# tornado-shield.net
KiCad netlist of a schematic drawn in EAGLE
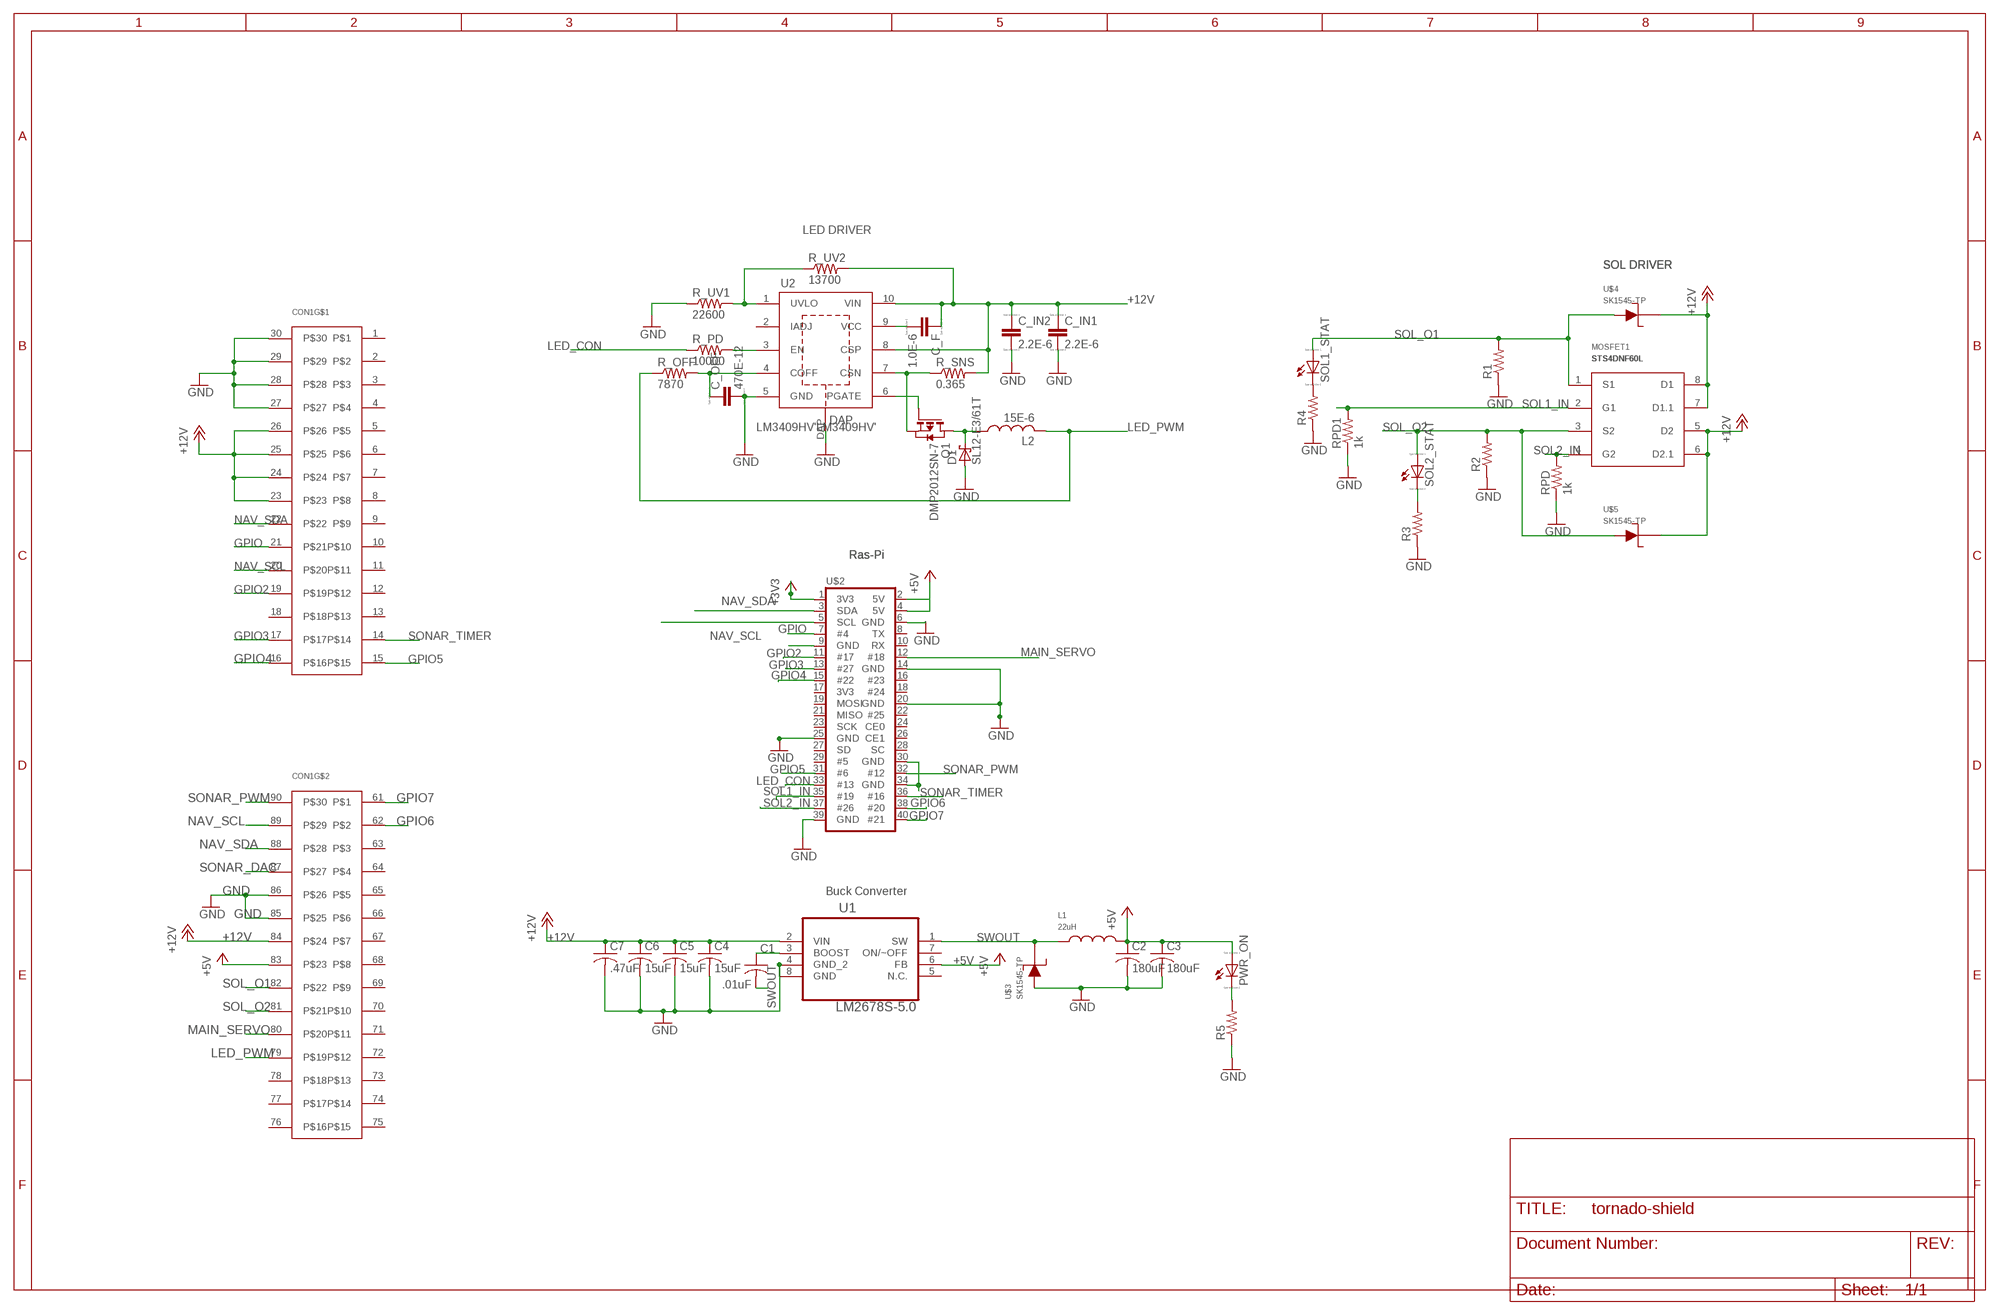
[diagram p0: schematic, sheet 1]

(export (version "E")
  (design (tool "Eeschema 10.0.6"))
  (components
    (comp (ref "C1")
      (value ".01uF")
      (footprint "eagle-import:C0603")
      (libsource (lib "eagle-import") (part "C-USC0603"))
    )
    (comp (ref "C2")
      (value "180uF")
      (footprint "eagle-import:C0603")
      (libsource (lib "eagle-import") (part "C-USC0603"))
    )
    (comp (ref "C3")
      (value "180uF")
      (footprint "eagle-import:C0603")
      (libsource (lib "eagle-import") (part "C-USC0603"))
    )
    (comp (ref "C4")
      (value "15uF")
      (footprint "eagle-import:C0603")
      (libsource (lib "eagle-import") (part "C-USC0603"))
    )
    (comp (ref "C5")
      (value "15uF")
      (footprint "eagle-import:C0603")
      (libsource (lib "eagle-import") (part "C-USC0603"))
    )
    (comp (ref "C6")
      (value "15uF")
      (footprint "eagle-import:C0603")
      (libsource (lib "eagle-import") (part "C-USC0603"))
    )
    (comp (ref "C7")
      (value ".47uF")
      (footprint "eagle-import:C0603")
      (libsource (lib "eagle-import") (part "C-USC0603"))
    )
    (comp (ref "CON1")
      (value "ROV_SHIELD_V2")
      (footprint "eagle-import:ROV_SHIELD_V2")
      (libsource (lib "eagle-import") (part "ROV_SHIELD_V2"))
    )
    (comp (ref "C_F")
      (value "1.0E-6")
      (footprint "eagle-import:C0603")
      (libsource (lib "eagle-import") (part "CC0603"))
    )
    (comp (ref "C_IN1")
      (value "2.2E-6")
      (footprint "eagle-import:C0603")
      (libsource (lib "eagle-import") (part "CC0603"))
    )
    (comp (ref "C_IN2")
      (value "2.2E-6")
      (footprint "eagle-import:C0603")
      (libsource (lib "eagle-import") (part "CC0603"))
    )
    (comp (ref "C_OFF")
      (value "470E-12")
      (footprint "eagle-import:C0402")
      (libsource (lib "eagle-import") (part "CC0402"))
    )
    (comp (ref "D1")
      (value "SL12-E3/61T")
      (footprint "eagle-import:SL12-E3_61T")
      (libsource (lib "eagle-import") (part "SL12-E3/61T"))
    )
    (comp (ref "L1")
      (value "22uH")
      (footprint "eagle-import:7443551221")
      (libsource (lib "eagle-import") (part "L_7443551221"))
    )
    (comp (ref "L2")
      (value "15E-6")
      (footprint "eagle-import:SRN8040")
      (libsource (lib "eagle-import") (part "SRN8040"))
    )
    (comp (ref "MOSFET1")
      (value "STS4DNF60L")
      (footprint "eagle-import:SO08")
      (libsource (lib "eagle-import") (part "STS4DNF60L"))
    )
    (comp (ref "PWR_ON")
      (value "LED_ESML0603")
      (footprint "eagle-import:LED_SML0603")
      (libsource (lib "eagle-import") (part "LED_ESML0603"))
    )
    (comp (ref "Q1")
      (value "DMP2012SN-7")
      (footprint "eagle-import:DMP2012SN-7")
      (libsource (lib "eagle-import") (part "DMP2012SN-7"))
    )
    (comp (ref "R1")
      (value "R-US_R0603")
      (footprint "eagle-import:R0603")
      (libsource (lib "eagle-import") (part "rcl_R-US_R0603"))
    )
    (comp (ref "R2")
      (value "R-US_R0603")
      (footprint "eagle-import:R0603")
      (libsource (lib "eagle-import") (part "rcl_R-US_R0603"))
    )
    (comp (ref "R3")
      (value "R-US_R0603")
      (footprint "eagle-import:R0603")
      (libsource (lib "eagle-import") (part "rcl_R-US_R0603"))
    )
    (comp (ref "R4")
      (value "R-US_R0603")
      (footprint "eagle-import:R0603")
      (libsource (lib "eagle-import") (part "rcl_R-US_R0603"))
    )
    (comp (ref "R5")
      (value "R-US_R0603")
      (footprint "eagle-import:R0603")
      (libsource (lib "eagle-import") (part "rcl_R-US_R0603"))
    )
    (comp (ref "RPD")
      (value "1k")
      (footprint "eagle-import:R0603")
      (libsource (lib "eagle-import") (part "R-US_R0603"))
    )
    (comp (ref "RPD1")
      (value "1k")
      (footprint "eagle-import:R0603")
      (libsource (lib "eagle-import") (part "R-US_R0603"))
    )
    (comp (ref "R_OFF")
      (value "7870")
      (footprint "eagle-import:R0603")
      (libsource (lib "eagle-import") (part "R-US_R0603"))
    )
    (comp (ref "R_PD")
      (value "10000")
      (footprint "eagle-import:R0603")
      (libsource (lib "eagle-import") (part "R-US_R0603"))
    )
    (comp (ref "R_SNS")
      (value "0.365")
      (footprint "eagle-import:R2512")
      (libsource (lib "eagle-import") (part "R-US_R2512"))
    )
    (comp (ref "R_UV1")
      (value "22600")
      (footprint "eagle-import:R0603")
      (libsource (lib "eagle-import") (part "R-US_R0603"))
    )
    (comp (ref "R_UV2")
      (value "13700")
      (footprint "eagle-import:R0603")
      (libsource (lib "eagle-import") (part "R-US_R0603"))
    )
    (comp (ref "SOL1_STAT")
      (value "LED_ESML0603")
      (footprint "eagle-import:LED_SML0603")
      (libsource (lib "eagle-import") (part "LED_ESML0603"))
    )
    (comp (ref "SOL2_STAT")
      (value "LED_ESML0603")
      (footprint "eagle-import:LED_SML0603")
      (libsource (lib "eagle-import") (part "LED_ESML0603"))
    )
    (comp (ref "U$2")
      (value "RASPBERRY-PI-2")
      (footprint "eagle-import:RASPBERRY-PI-2")
      (libsource (lib "eagle-import") (part "RASPBERRY-PI-2"))
    )
    (comp (ref "U$3")
      (value "SK1545-TP")
      (footprint "eagle-import:DO-214AB")
      (libsource (lib "eagle-import") (part "SK1545-TP"))
    )
    (comp (ref "U$4")
      (value "SK1545-TP")
      (footprint "eagle-import:DO-214AB")
      (libsource (lib "eagle-import") (part "SK1545-TP"))
    )
    (comp (ref "U$5")
      (value "SK1545-TP")
      (footprint "eagle-import:DO-214AB")
      (libsource (lib "eagle-import") (part "SK1545-TP"))
    )
    (comp (ref "U1")
      (value "LM2678S-5.0")
      (footprint "eagle-import:TO127P1435X457-8N")
      (libsource (lib "eagle-import") (part "LM2678S-5.0"))
    )
    (comp (ref "U2")
      (value "LM3409HV'LM3409HV'")
      (footprint "eagle-import:VSSOP-10")
      (libsource (lib "eagle-import") (part "LM3409HV'LM3409HV'"))
    )
  )
  (nets
    (net (code "1") (name "+3V3") (class "Default")
      (node (ref "U$2") (pin "1") (pinfunction "3V3_1") (pintype "bidirectional"))
    )
    (net (code "2") (name "+5V") (class "Default")
      (node (ref "C2") (pin "1") (pinfunction "1_1") (pintype "passive"))
      (node (ref "C3") (pin "1") (pinfunction "1_1") (pintype "passive"))
      (node (ref "CON1") (pin "83") (pinfunction "P$23_83") (pintype "bidirectional"))
      (node (ref "L1") (pin "P$2") (pinfunction "P$2_P$2") (pintype "bidirectional"))
      (node (ref "PWR_ON") (pin "A") (pinfunction "A_A") (pintype "passive"))
      (node (ref "U$2") (pin "2") (pinfunction "5V_2") (pintype "bidirectional"))
      (node (ref "U$2") (pin "4") (pinfunction "5V_4") (pintype "bidirectional"))
      (node (ref "U1") (pin "6") (pinfunction "FB_6") (pintype "passive"))
    )
    (net (code "3") (name "+12V") (class "Default")
      (node (ref "C4") (pin "1") (pinfunction "1_1") (pintype "passive"))
      (node (ref "C5") (pin "1") (pinfunction "1_1") (pintype "passive"))
      (node (ref "C6") (pin "1") (pinfunction "1_1") (pintype "passive"))
      (node (ref "C7") (pin "1") (pinfunction "1_1") (pintype "passive"))
      (node (ref "CON1") (pin "23") (pinfunction "P$23_23") (pintype "bidirectional"))
      (node (ref "CON1") (pin "24") (pinfunction "P$24_24") (pintype "bidirectional"))
      (node (ref "CON1") (pin "25") (pinfunction "P$25_25") (pintype "bidirectional"))
      (node (ref "CON1") (pin "26") (pinfunction "P$26_26") (pintype "bidirectional"))
      (node (ref "CON1") (pin "84") (pinfunction "P$24_84") (pintype "bidirectional"))
      (node (ref "C_F") (pin "1") (pinfunction "1_1") (pintype "passive"))
      (node (ref "C_IN1") (pin "1") (pinfunction "1_1") (pintype "passive"))
      (node (ref "C_IN2") (pin "1") (pinfunction "1_1") (pintype "passive"))
      (node (ref "MOSFET1") (pin "5") (pinfunction "D2_5") (pintype "bidirectional"))
      (node (ref "MOSFET1") (pin "6") (pinfunction "D2.1_6") (pintype "bidirectional"))
      (node (ref "MOSFET1") (pin "7") (pinfunction "D1.1_7") (pintype "bidirectional"))
      (node (ref "MOSFET1") (pin "8") (pinfunction "D1_8") (pintype "bidirectional"))
      (node (ref "R_SNS") (pin "2") (pinfunction "2_2") (pintype "passive"))
      (node (ref "R_UV2") (pin "2") (pinfunction "2_2") (pintype "passive"))
      (node (ref "U$4") (pin "P$2") (pinfunction "P$2_P$2") (pintype "bidirectional"))
      (node (ref "U$5") (pin "P$2") (pinfunction "P$2_P$2") (pintype "bidirectional"))
      (node (ref "U1") (pin "2") (pinfunction "VIN_2") (pintype "input"))
      (node (ref "U2") (pin "10") (pinfunction "VIN_10") (pintype "bidirectional"))
      (node (ref "U2") (pin "8") (pinfunction "CSP_8") (pintype "bidirectional"))
    )
    (net (code "4") (name "/GPIO") (class "Default")
      (node (ref "CON1") (pin "21") (pinfunction "P$21_21") (pintype "bidirectional"))
      (node (ref "U$2") (pin "7") (pinfunction "#4_7") (pintype "bidirectional"))
    )
    (net (code "5") (name "/GPIO2") (class "Default")
      (node (ref "CON1") (pin "19") (pinfunction "P$19_19") (pintype "bidirectional"))
      (node (ref "U$2") (pin "11") (pinfunction "#17_11") (pintype "bidirectional"))
    )
    (net (code "6") (name "/GPIO3") (class "Default")
      (node (ref "CON1") (pin "17") (pinfunction "P$17_17") (pintype "bidirectional"))
      (node (ref "U$2") (pin "13") (pinfunction "#27_13") (pintype "bidirectional"))
    )
    (net (code "7") (name "/GPIO4") (class "Default")
      (node (ref "CON1") (pin "16") (pinfunction "P$16_16") (pintype "bidirectional"))
      (node (ref "U$2") (pin "15") (pinfunction "#22_15") (pintype "bidirectional"))
    )
    (net (code "8") (name "/GPIO5") (class "Default")
      (node (ref "CON1") (pin "15") (pinfunction "P$15_15") (pintype "bidirectional"))
      (node (ref "U$2") (pin "31") (pinfunction "#6_31") (pintype "bidirectional"))
    )
    (net (code "9") (name "/GPIO6") (class "Default")
      (node (ref "CON1") (pin "62") (pinfunction "P$2_62") (pintype "bidirectional"))
      (node (ref "U$2") (pin "38") (pinfunction "#20_38") (pintype "bidirectional"))
    )
    (net (code "10") (name "/GPIO7") (class "Default")
      (node (ref "CON1") (pin "61") (pinfunction "P$1_61") (pintype "bidirectional"))
      (node (ref "U$2") (pin "40") (pinfunction "#21_40") (pintype "bidirectional"))
    )
    (net (code "11") (name "/LED_CON") (class "Default")
      (node (ref "R_PD") (pin "1") (pinfunction "1_1") (pintype "passive"))
      (node (ref "U$2") (pin "33") (pinfunction "#13_33") (pintype "bidirectional"))
    )
    (net (code "12") (name "/LED_PWM") (class "Default")
      (node (ref "CON1") (pin "79") (pinfunction "P$19_79") (pintype "bidirectional"))
      (node (ref "L2") (pin "2") (pinfunction "2_2") (pintype "passive"))
      (node (ref "R_OFF") (pin "1") (pinfunction "1_1") (pintype "passive"))
    )
    (net (code "13") (name "/MAIN_SERVO") (class "Default")
      (node (ref "CON1") (pin "80") (pinfunction "P$20_80") (pintype "bidirectional"))
      (node (ref "U$2") (pin "12") (pinfunction "#18_12") (pintype "bidirectional"))
    )
    (net (code "14") (name "/NAV_SCL") (class "Default")
      (node (ref "CON1") (pin "20") (pinfunction "P$20_20") (pintype "bidirectional"))
      (node (ref "CON1") (pin "89") (pinfunction "P$29_89") (pintype "bidirectional"))
      (node (ref "U$2") (pin "5") (pinfunction "SCL_5") (pintype "bidirectional"))
    )
    (net (code "15") (name "/NAV_SDA") (class "Default")
      (node (ref "CON1") (pin "22") (pinfunction "P$22_22") (pintype "bidirectional"))
      (node (ref "CON1") (pin "88") (pinfunction "P$28_88") (pintype "bidirectional"))
      (node (ref "U$2") (pin "3") (pinfunction "SDA_3") (pintype "bidirectional"))
    )
    (net (code "16") (name "/SOL1_IN") (class "Default")
      (node (ref "MOSFET1") (pin "2") (pinfunction "G1_2") (pintype "bidirectional"))
      (node (ref "RPD1") (pin "2") (pinfunction "2_2") (pintype "passive"))
      (node (ref "U$2") (pin "35") (pinfunction "#19_35") (pintype "bidirectional"))
    )
    (net (code "17") (name "/SOL2_IN") (class "Default")
      (node (ref "MOSFET1") (pin "4") (pinfunction "G2_4") (pintype "bidirectional"))
      (node (ref "RPD") (pin "2") (pinfunction "2_2") (pintype "passive"))
      (node (ref "U$2") (pin "37") (pinfunction "#26_37") (pintype "bidirectional"))
    )
    (net (code "18") (name "/SOL_O1") (class "Default")
      (node (ref "CON1") (pin "82") (pinfunction "P$22_82") (pintype "bidirectional"))
      (node (ref "MOSFET1") (pin "1") (pinfunction "S1_1") (pintype "bidirectional"))
      (node (ref "R1") (pin "2") (pinfunction "2_2") (pintype "passive"))
      (node (ref "SOL1_STAT") (pin "A") (pinfunction "A_A") (pintype "passive"))
      (node (ref "U$4") (pin "P$1") (pinfunction "P$1_P$1") (pintype "bidirectional"))
    )
    (net (code "19") (name "/SOL_O2") (class "Default")
      (node (ref "CON1") (pin "81") (pinfunction "P$21_81") (pintype "bidirectional"))
      (node (ref "MOSFET1") (pin "3") (pinfunction "S2_3") (pintype "bidirectional"))
      (node (ref "R2") (pin "2") (pinfunction "2_2") (pintype "passive"))
      (node (ref "SOL2_STAT") (pin "A") (pinfunction "A_A") (pintype "passive"))
      (node (ref "U$5") (pin "P$1") (pinfunction "P$1_P$1") (pintype "bidirectional"))
    )
    (net (code "20") (name "/SONAR_DAC") (class "Default")
      (node (ref "CON1") (pin "87") (pinfunction "P$27_87") (pintype "bidirectional"))
    )
    (net (code "21") (name "/SONAR_PWM") (class "Default")
      (node (ref "CON1") (pin "90") (pinfunction "P$30_90") (pintype "bidirectional"))
      (node (ref "U$2") (pin "32") (pinfunction "#12_32") (pintype "bidirectional"))
    )
    (net (code "22") (name "/SONAR_TIMER") (class "Default")
      (node (ref "CON1") (pin "14") (pinfunction "P$14_14") (pintype "bidirectional"))
      (node (ref "U$2") (pin "36") (pinfunction "#16_36") (pintype "bidirectional"))
    )
    (net (code "23") (name "/SWOUT") (class "Default")
      (node (ref "C1") (pin "2") (pinfunction "2_2") (pintype "passive"))
      (node (ref "L1") (pin "P$1") (pinfunction "P$1_P$1") (pintype "bidirectional"))
      (node (ref "U$3") (pin "P$2") (pinfunction "P$2_P$2") (pintype "bidirectional"))
      (node (ref "U1") (pin "1") (pinfunction "SW_1") (pintype "output"))
    )
    (net (code "24") (name "GND") (class "Default")
      (node (ref "C2") (pin "2") (pinfunction "2_2") (pintype "passive"))
      (node (ref "C3") (pin "2") (pinfunction "2_2") (pintype "passive"))
      (node (ref "C4") (pin "2") (pinfunction "2_2") (pintype "passive"))
      (node (ref "C5") (pin "2") (pinfunction "2_2") (pintype "passive"))
      (node (ref "C6") (pin "2") (pinfunction "2_2") (pintype "passive"))
      (node (ref "C7") (pin "2") (pinfunction "2_2") (pintype "passive"))
      (node (ref "CON1") (pin "27") (pinfunction "P$27_27") (pintype "bidirectional"))
      (node (ref "CON1") (pin "28") (pinfunction "P$28_28") (pintype "bidirectional"))
      (node (ref "CON1") (pin "29") (pinfunction "P$29_29") (pintype "bidirectional"))
      (node (ref "CON1") (pin "30") (pinfunction "P$30_30") (pintype "bidirectional"))
      (node (ref "CON1") (pin "85") (pinfunction "P$25_85") (pintype "bidirectional"))
      (node (ref "CON1") (pin "86") (pinfunction "P$26_86") (pintype "bidirectional"))
      (node (ref "C_IN1") (pin "2") (pinfunction "2_2") (pintype "passive"))
      (node (ref "C_IN2") (pin "2") (pinfunction "2_2") (pintype "passive"))
      (node (ref "C_OFF") (pin "2") (pinfunction "2_2") (pintype "passive"))
      (node (ref "D1") (pin "2") (pinfunction "A_2") (pintype "passive"))
      (node (ref "R1") (pin "1") (pinfunction "1_1") (pintype "passive"))
      (node (ref "R2") (pin "1") (pinfunction "1_1") (pintype "passive"))
      (node (ref "R3") (pin "1") (pinfunction "1_1") (pintype "passive"))
      (node (ref "R4") (pin "1") (pinfunction "1_1") (pintype "passive"))
      (node (ref "R5") (pin "1") (pinfunction "1_1") (pintype "passive"))
      (node (ref "RPD") (pin "1") (pinfunction "1_1") (pintype "passive"))
      (node (ref "RPD1") (pin "1") (pinfunction "1_1") (pintype "passive"))
      (node (ref "R_UV1") (pin "1") (pinfunction "1_1") (pintype "passive"))
      (node (ref "U$2") (pin "14") (pinfunction "GND_14") (pintype "bidirectional"))
      (node (ref "U$2") (pin "20") (pinfunction "GND_20") (pintype "bidirectional"))
      (node (ref "U$2") (pin "25") (pinfunction "GND_25") (pintype "bidirectional"))
      (node (ref "U$2") (pin "30") (pinfunction "GND_30") (pintype "bidirectional"))
      (node (ref "U$2") (pin "34") (pinfunction "GND_34") (pintype "bidirectional"))
      (node (ref "U$2") (pin "39") (pinfunction "GND_39") (pintype "bidirectional"))
      (node (ref "U$2") (pin "6") (pinfunction "GND_6") (pintype "bidirectional"))
      (node (ref "U$2") (pin "9") (pinfunction "GND_9") (pintype "bidirectional"))
      (node (ref "U$3") (pin "P$1") (pinfunction "P$1_P$1") (pintype "bidirectional"))
      (node (ref "U1") (pin "4") (pinfunction "GND_2_4") (pintype "passive"))
      (node (ref "U1") (pin "8") (pinfunction "GND_8") (pintype "passive"))
      (node (ref "U2") (pin "5") (pinfunction "GND_5") (pintype "bidirectional"))
      (node (ref "U2") (pin "DAP") (pinfunction "DAP_DAP") (pintype "bidirectional"))
    )
    (net (code "25") (name "Net-(D1-C)") (class "Default")
      (node (ref "D1") (pin "1") (pinfunction "C_1") (pintype "passive"))
      (node (ref "L2") (pin "1") (pinfunction "1_1") (pintype "passive"))
      (node (ref "Q1") (pin "1") (pinfunction "D_1") (pintype "passive"))
    )
    (net (code "26") (name "Net-(PWR_ON-PadC)") (class "Default")
      (node (ref "PWR_ON") (pin "C") (pinfunction "C_C") (pintype "passive"))
      (node (ref "R5") (pin "2") (pinfunction "2_2") (pintype "passive"))
    )
    (net (code "27") (name "Net-(Q1-G)") (class "Default")
      (node (ref "Q1") (pin "2") (pinfunction "G_2") (pintype "passive"))
      (node (ref "U2") (pin "6") (pinfunction "PGATE_6") (pintype "bidirectional"))
    )
    (net (code "28") (name "Net-(Q1-S)") (class "Default")
      (node (ref "Q1") (pin "3") (pinfunction "S_3") (pintype "passive"))
      (node (ref "R_SNS") (pin "1") (pinfunction "1_1") (pintype "passive"))
      (node (ref "U2") (pin "7") (pinfunction "CSN_7") (pintype "bidirectional"))
    )
    (net (code "29") (name "Net-(R3-Pad2)") (class "Default")
      (node (ref "R3") (pin "2") (pinfunction "2_2") (pintype "passive"))
      (node (ref "SOL2_STAT") (pin "C") (pinfunction "C_C") (pintype "passive"))
    )
    (net (code "30") (name "Net-(R4-Pad2)") (class "Default")
      (node (ref "R4") (pin "2") (pinfunction "2_2") (pintype "passive"))
      (node (ref "SOL1_STAT") (pin "C") (pinfunction "C_C") (pintype "passive"))
    )
    (net (code "31") (name "Net-(U1-BOOST)") (class "Default")
      (node (ref "C1") (pin "1") (pinfunction "1_1") (pintype "passive"))
      (node (ref "U1") (pin "3") (pinfunction "BOOST_3") (pintype "passive"))
    )
    (net (code "32") (name "Net-(U2-COFF)") (class "Default")
      (node (ref "C_OFF") (pin "1") (pinfunction "1_1") (pintype "passive"))
      (node (ref "R_OFF") (pin "2") (pinfunction "2_2") (pintype "passive"))
      (node (ref "U2") (pin "4") (pinfunction "COFF_4") (pintype "bidirectional"))
    )
    (net (code "33") (name "Net-(U2-EN)") (class "Default")
      (node (ref "R_PD") (pin "2") (pinfunction "2_2") (pintype "passive"))
      (node (ref "U2") (pin "3") (pinfunction "EN_3") (pintype "bidirectional"))
    )
    (net (code "34") (name "Net-(U2-UVLO)") (class "Default")
      (node (ref "R_UV1") (pin "2") (pinfunction "2_2") (pintype "passive"))
      (node (ref "R_UV2") (pin "1") (pinfunction "1_1") (pintype "passive"))
      (node (ref "U2") (pin "1") (pinfunction "UVLO_1") (pintype "bidirectional"))
    )
    (net (code "35") (name "Net-(U2-VCC)") (class "Default")
      (node (ref "C_F") (pin "2") (pinfunction "2_2") (pintype "passive"))
      (node (ref "U2") (pin "9") (pinfunction "VCC_9") (pintype "bidirectional"))
    )
    (net (code "36") (name "unconnected-(CON1A-P$1-Pad1)") (class "Default")
      (node (ref "CON1") (pin "1") (pinfunction "P$1_1") (pintype "bidirectional"))
    )
    (net (code "37") (name "unconnected-(CON1A-P$2-Pad2)") (class "Default")
      (node (ref "CON1") (pin "2") (pinfunction "P$2_2") (pintype "bidirectional"))
    )
    (net (code "38") (name "unconnected-(CON1A-P$3-Pad3)") (class "Default")
      (node (ref "CON1") (pin "3") (pinfunction "P$3_3") (pintype "bidirectional"))
    )
    (net (code "39") (name "unconnected-(CON1A-P$4-Pad4)") (class "Default")
      (node (ref "CON1") (pin "4") (pinfunction "P$4_4") (pintype "bidirectional"))
    )
    (net (code "40") (name "unconnected-(CON1A-P$5-Pad5)") (class "Default")
      (node (ref "CON1") (pin "5") (pinfunction "P$5_5") (pintype "bidirectional"))
    )
    (net (code "41") (name "unconnected-(CON1A-P$6-Pad6)") (class "Default")
      (node (ref "CON1") (pin "6") (pinfunction "P$6_6") (pintype "bidirectional"))
    )
    (net (code "42") (name "unconnected-(CON1A-P$7-Pad7)") (class "Default")
      (node (ref "CON1") (pin "7") (pinfunction "P$7_7") (pintype "bidirectional"))
    )
    (net (code "43") (name "unconnected-(CON1A-P$8-Pad8)") (class "Default")
      (node (ref "CON1") (pin "8") (pinfunction "P$8_8") (pintype "bidirectional"))
    )
    (net (code "44") (name "unconnected-(CON1A-P$9-Pad9)") (class "Default")
      (node (ref "CON1") (pin "9") (pinfunction "P$9_9") (pintype "bidirectional"))
    )
    (net (code "45") (name "unconnected-(CON1A-P$10-Pad10)") (class "Default")
      (node (ref "CON1") (pin "10") (pinfunction "P$10_10") (pintype "bidirectional"))
    )
    (net (code "46") (name "unconnected-(CON1A-P$11-Pad11)") (class "Default")
      (node (ref "CON1") (pin "11") (pinfunction "P$11_11") (pintype "bidirectional"))
    )
    (net (code "47") (name "unconnected-(CON1A-P$12-Pad12)") (class "Default")
      (node (ref "CON1") (pin "12") (pinfunction "P$12_12") (pintype "bidirectional"))
    )
    (net (code "48") (name "unconnected-(CON1A-P$13-Pad13)") (class "Default")
      (node (ref "CON1") (pin "13") (pinfunction "P$13_13") (pintype "bidirectional"))
    )
    (net (code "49") (name "unconnected-(CON1A-P$18-Pad18)") (class "Default")
      (node (ref "CON1") (pin "18") (pinfunction "P$18_18") (pintype "bidirectional"))
    )
    (net (code "50") (name "unconnected-(CON1B-P$3-Pad63)") (class "Default")
      (node (ref "CON1") (pin "63") (pinfunction "P$3_63") (pintype "bidirectional"))
    )
    (net (code "51") (name "unconnected-(CON1B-P$4-Pad64)") (class "Default")
      (node (ref "CON1") (pin "64") (pinfunction "P$4_64") (pintype "bidirectional"))
    )
    (net (code "52") (name "unconnected-(CON1B-P$5-Pad65)") (class "Default")
      (node (ref "CON1") (pin "65") (pinfunction "P$5_65") (pintype "bidirectional"))
    )
    (net (code "53") (name "unconnected-(CON1B-P$6-Pad66)") (class "Default")
      (node (ref "CON1") (pin "66") (pinfunction "P$6_66") (pintype "bidirectional"))
    )
    (net (code "54") (name "unconnected-(CON1B-P$7-Pad67)") (class "Default")
      (node (ref "CON1") (pin "67") (pinfunction "P$7_67") (pintype "bidirectional"))
    )
    (net (code "55") (name "unconnected-(CON1B-P$8-Pad68)") (class "Default")
      (node (ref "CON1") (pin "68") (pinfunction "P$8_68") (pintype "bidirectional"))
    )
    (net (code "56") (name "unconnected-(CON1B-P$9-Pad69)") (class "Default")
      (node (ref "CON1") (pin "69") (pinfunction "P$9_69") (pintype "bidirectional"))
    )
    (net (code "57") (name "unconnected-(CON1B-P$10-Pad70)") (class "Default")
      (node (ref "CON1") (pin "70") (pinfunction "P$10_70") (pintype "bidirectional"))
    )
    (net (code "58") (name "unconnected-(CON1B-P$11-Pad71)") (class "Default")
      (node (ref "CON1") (pin "71") (pinfunction "P$11_71") (pintype "bidirectional"))
    )
    (net (code "59") (name "unconnected-(CON1B-P$12-Pad72)") (class "Default")
      (node (ref "CON1") (pin "72") (pinfunction "P$12_72") (pintype "bidirectional"))
    )
    (net (code "60") (name "unconnected-(CON1B-P$13-Pad73)") (class "Default")
      (node (ref "CON1") (pin "73") (pinfunction "P$13_73") (pintype "bidirectional"))
    )
    (net (code "61") (name "unconnected-(CON1B-P$14-Pad74)") (class "Default")
      (node (ref "CON1") (pin "74") (pinfunction "P$14_74") (pintype "bidirectional"))
    )
    (net (code "62") (name "unconnected-(CON1B-P$15-Pad75)") (class "Default")
      (node (ref "CON1") (pin "75") (pinfunction "P$15_75") (pintype "bidirectional"))
    )
    (net (code "63") (name "unconnected-(CON1B-P$16-Pad76)") (class "Default")
      (node (ref "CON1") (pin "76") (pinfunction "P$16_76") (pintype "bidirectional"))
    )
    (net (code "64") (name "unconnected-(CON1B-P$17-Pad77)") (class "Default")
      (node (ref "CON1") (pin "77") (pinfunction "P$17_77") (pintype "bidirectional"))
    )
    (net (code "65") (name "unconnected-(CON1B-P$18-Pad78)") (class "Default")
      (node (ref "CON1") (pin "78") (pinfunction "P$18_78") (pintype "bidirectional"))
    )
    (net (code "66") (name "unconnected-(U$2-#5-Pad29)") (class "Default")
      (node (ref "U$2") (pin "29") (pinfunction "#5_29") (pintype "bidirectional"))
    )
    (net (code "67") (name "unconnected-(U$2-#23-Pad16)") (class "Default")
      (node (ref "U$2") (pin "16") (pinfunction "#23_16") (pintype "bidirectional"))
    )
    (net (code "68") (name "unconnected-(U$2-#24-Pad18)") (class "Default")
      (node (ref "U$2") (pin "18") (pinfunction "#24_18") (pintype "bidirectional"))
    )
    (net (code "69") (name "unconnected-(U$2-#25-Pad22)") (class "Default")
      (node (ref "U$2") (pin "22") (pinfunction "#25_22") (pintype "bidirectional"))
    )
    (net (code "70") (name "unconnected-(U$2-3V3-Pad17)") (class "Default")
      (node (ref "U$2") (pin "17") (pinfunction "3V3_17") (pintype "bidirectional"))
    )
    (net (code "71") (name "unconnected-(U$2-CE0-Pad24)") (class "Default")
      (node (ref "U$2") (pin "24") (pinfunction "CE0_24") (pintype "bidirectional"))
    )
    (net (code "72") (name "unconnected-(U$2-CE1-Pad26)") (class "Default")
      (node (ref "U$2") (pin "26") (pinfunction "CE1_26") (pintype "bidirectional"))
    )
    (net (code "73") (name "unconnected-(U$2-MISO-Pad21)") (class "Default")
      (node (ref "U$2") (pin "21") (pinfunction "MISO_21") (pintype "bidirectional"))
    )
    (net (code "74") (name "unconnected-(U$2-MOSI-Pad19)") (class "Default")
      (node (ref "U$2") (pin "19") (pinfunction "MOSI_19") (pintype "bidirectional"))
    )
    (net (code "75") (name "unconnected-(U$2-RX-Pad10)") (class "Default")
      (node (ref "U$2") (pin "10") (pinfunction "RX_10") (pintype "bidirectional"))
    )
    (net (code "76") (name "unconnected-(U$2-SC-Pad28)") (class "Default")
      (node (ref "U$2") (pin "28") (pinfunction "SC_28") (pintype "bidirectional"))
    )
    (net (code "77") (name "unconnected-(U$2-SCK-Pad23)") (class "Default")
      (node (ref "U$2") (pin "23") (pinfunction "SCK_23") (pintype "bidirectional"))
    )
    (net (code "78") (name "unconnected-(U$2-SD-Pad27)") (class "Default")
      (node (ref "U$2") (pin "27") (pinfunction "SD_27") (pintype "bidirectional"))
    )
    (net (code "79") (name "unconnected-(U$2-TX-Pad8)") (class "Default")
      (node (ref "U$2") (pin "8") (pinfunction "TX_8") (pintype "bidirectional"))
    )
    (net (code "80") (name "unconnected-(U1-N.C.-Pad5)") (class "Default")
      (node (ref "U1") (pin "5") (pinfunction "N.C._5") (pintype "passive"))
    )
    (net (code "81") (name "unconnected-(U1-ON{slash}~{OFF}-Pad7)") (class "Default")
      (node (ref "U1") (pin "7") (pinfunction "ON/~{OFF}_7") (pintype "passive"))
    )
    (net (code "82") (name "unconnected-(U2-IADJ-Pad2)") (class "Default")
      (node (ref "U2") (pin "2") (pinfunction "IADJ_2") (pintype "bidirectional"))
    )
  )
)
